# Dual_OTA_VCA.net
KiCad netlist of a schematic drawn in EAGLE
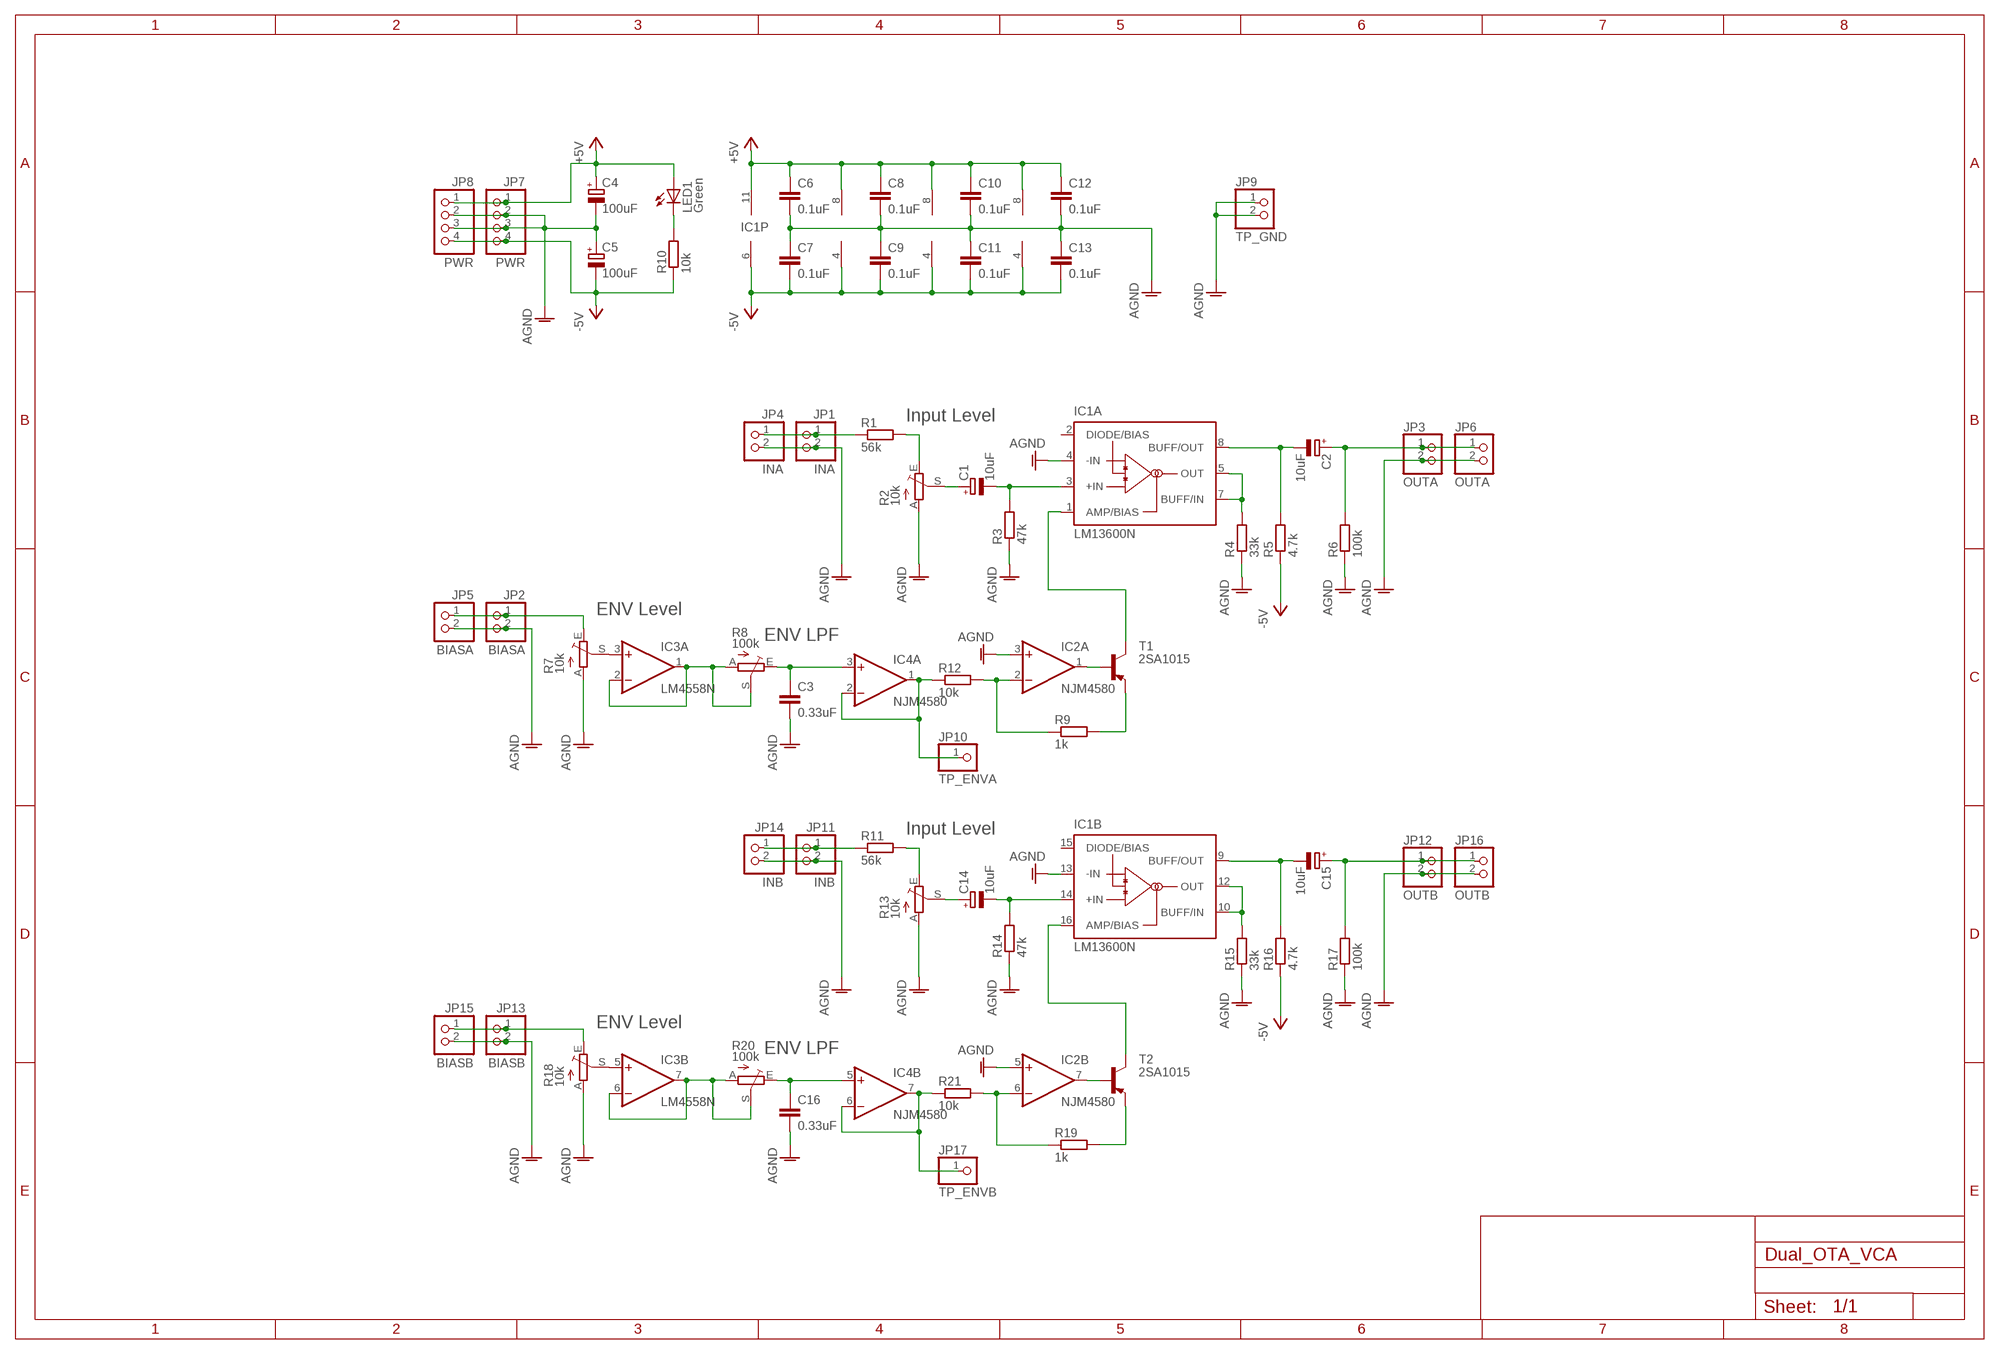
[diagram p0: schematic, sheet 1]

(export (version "E")
  (design (tool "Eeschema 10.0.6"))
  (components
    (comp (ref "C1")
      (value "10uF")
      (footprint "eagle-import:E2,5-7")
      (libsource (lib "eagle-import") (part "CPOL-EUE2.5-7"))
    )
    (comp (ref "C2")
      (value "10uF")
      (footprint "eagle-import:E2,5-7")
      (libsource (lib "eagle-import") (part "CPOL-EUE2.5-7"))
    )
    (comp (ref "C3")
      (value "0.33uF")
      (footprint "eagle-import:C050-030X075")
      (libsource (lib "eagle-import") (part "C-EU050-030X075"))
    )
    (comp (ref "C4")
      (value "100uF")
      (footprint "eagle-import:E2,5-7")
      (libsource (lib "eagle-import") (part "CPOL-EUE2.5-7"))
    )
    (comp (ref "C5")
      (value "100uF")
      (footprint "eagle-import:E2,5-7")
      (libsource (lib "eagle-import") (part "CPOL-EUE2.5-7"))
    )
    (comp (ref "C6")
      (value "0.1uF")
      (footprint "eagle-import:C050-024X044")
      (libsource (lib "eagle-import") (part "C-EU050-024X044"))
    )
    (comp (ref "C7")
      (value "0.1uF")
      (footprint "eagle-import:C050-024X044")
      (libsource (lib "eagle-import") (part "C-EU050-024X044"))
    )
    (comp (ref "C8")
      (value "0.1uF")
      (footprint "eagle-import:C025-024X044")
      (libsource (lib "eagle-import") (part "C-EU025-024X044"))
    )
    (comp (ref "C9")
      (value "0.1uF")
      (footprint "eagle-import:C025-024X044")
      (libsource (lib "eagle-import") (part "C-EU025-024X044"))
    )
    (comp (ref "C10")
      (value "0.1uF")
      (footprint "eagle-import:C025-024X044")
      (libsource (lib "eagle-import") (part "C-EU025-024X044"))
    )
    (comp (ref "C11")
      (value "0.1uF")
      (footprint "eagle-import:C025-024X044")
      (libsource (lib "eagle-import") (part "C-EU025-024X044"))
    )
    (comp (ref "C12")
      (value "0.1uF")
      (footprint "eagle-import:C025-024X044")
      (libsource (lib "eagle-import") (part "C-EU025-024X044"))
    )
    (comp (ref "C13")
      (value "0.1uF")
      (footprint "eagle-import:C025-024X044")
      (libsource (lib "eagle-import") (part "C-EU025-024X044"))
    )
    (comp (ref "C14")
      (value "10uF")
      (footprint "eagle-import:E2,5-7")
      (libsource (lib "eagle-import") (part "CPOL-EUE2.5-7"))
    )
    (comp (ref "C15")
      (value "10uF")
      (footprint "eagle-import:E2,5-7")
      (libsource (lib "eagle-import") (part "CPOL-EUE2.5-7"))
    )
    (comp (ref "C16")
      (value "0.33uF")
      (footprint "eagle-import:C050-030X075")
      (libsource (lib "eagle-import") (part "C-EU050-030X075"))
    )
    (comp (ref "IC1")
      (value "LM13600N")
      (footprint "eagle-import:DIL16")
      (libsource (lib "eagle-import") (part "LM13600N"))
    )
    (comp (ref "IC2")
      (value "NJM4580")
      (footprint "eagle-import:DIL08")
      (libsource (lib "eagle-import") (part "4558NLM"))
    )
    (comp (ref "IC3")
      (value "LM4558N")
      (footprint "eagle-import:DIL08")
      (libsource (lib "eagle-import") (part "4558NLM"))
    )
    (comp (ref "IC4")
      (value "NJM4580")
      (footprint "eagle-import:DIL08")
      (libsource (lib "eagle-import") (part "4558NLM"))
    )
    (comp (ref "JP1")
      (value "INA")
      (footprint "eagle-import:1X02")
      (libsource (lib "eagle-import") (part "PINHD-1X2"))
    )
    (comp (ref "JP2")
      (value "BIASA")
      (footprint "eagle-import:1X02")
      (libsource (lib "eagle-import") (part "PINHD-1X2"))
    )
    (comp (ref "JP3")
      (value "OUTA")
      (footprint "eagle-import:1X02")
      (libsource (lib "eagle-import") (part "PINHD-1X2"))
    )
    (comp (ref "JP4")
      (value "INA")
      (footprint "eagle-import:1X02")
      (libsource (lib "eagle-import") (part "PINHD-1X2"))
    )
    (comp (ref "JP5")
      (value "BIASA")
      (footprint "eagle-import:1X02")
      (libsource (lib "eagle-import") (part "PINHD-1X2"))
    )
    (comp (ref "JP6")
      (value "OUTA")
      (footprint "eagle-import:1X02")
      (libsource (lib "eagle-import") (part "PINHD-1X2"))
    )
    (comp (ref "JP7")
      (value "PWR")
      (footprint "eagle-import:1X04")
      (libsource (lib "eagle-import") (part "PINHD-1X4"))
    )
    (comp (ref "JP8")
      (value "PWR")
      (footprint "eagle-import:1X04")
      (libsource (lib "eagle-import") (part "PINHD-1X4"))
    )
    (comp (ref "JP9")
      (value "TP_GND")
      (footprint "eagle-import:1X02")
      (libsource (lib "eagle-import") (part "PINHD-1X2"))
    )
    (comp (ref "JP10")
      (value "TP_ENVA")
      (footprint "eagle-import:1X01")
      (libsource (lib "eagle-import") (part "PINHD-1X1"))
    )
    (comp (ref "JP11")
      (value "INB")
      (footprint "eagle-import:1X02")
      (libsource (lib "eagle-import") (part "PINHD-1X2"))
    )
    (comp (ref "JP12")
      (value "OUTB")
      (footprint "eagle-import:1X02")
      (libsource (lib "eagle-import") (part "PINHD-1X2"))
    )
    (comp (ref "JP13")
      (value "BIASB")
      (footprint "eagle-import:1X02")
      (libsource (lib "eagle-import") (part "PINHD-1X2"))
    )
    (comp (ref "JP14")
      (value "INB")
      (footprint "eagle-import:1X02")
      (libsource (lib "eagle-import") (part "PINHD-1X2"))
    )
    (comp (ref "JP15")
      (value "BIASB")
      (footprint "eagle-import:1X02")
      (libsource (lib "eagle-import") (part "PINHD-1X2"))
    )
    (comp (ref "JP16")
      (value "OUTB")
      (footprint "eagle-import:1X02")
      (libsource (lib "eagle-import") (part "PINHD-1X2"))
    )
    (comp (ref "JP17")
      (value "TP_ENVB")
      (footprint "eagle-import:1X01")
      (libsource (lib "eagle-import") (part "PINHD-1X1"))
    )
    (comp (ref "LED1")
      (value "Green")
      (footprint "eagle-import:LED3MM")
      (libsource (lib "eagle-import") (part "LED3MM"))
    )
    (comp (ref "R1")
      (value "56k")
      (footprint "eagle-import:0207_7")
      (libsource (lib "eagle-import") (part "R-EU_0207/7"))
    )
    (comp (ref "R2")
      (value "10k")
      (footprint "eagle-import:B25P")
      (libsource (lib "eagle-import") (part "TRIM_EU-B25P"))
    )
    (comp (ref "R3")
      (value "47k")
      (footprint "eagle-import:0207_7")
      (libsource (lib "eagle-import") (part "R-EU_0207/7"))
    )
    (comp (ref "R4")
      (value "33k")
      (footprint "eagle-import:0207_7")
      (libsource (lib "eagle-import") (part "R-EU_0207/7"))
    )
    (comp (ref "R5")
      (value "4.7k")
      (footprint "eagle-import:0207_7")
      (libsource (lib "eagle-import") (part "R-EU_0207/7"))
    )
    (comp (ref "R6")
      (value "100k")
      (footprint "eagle-import:0207_7")
      (libsource (lib "eagle-import") (part "R-EU_0207/7"))
    )
    (comp (ref "R7")
      (value "10k")
      (footprint "eagle-import:B25P")
      (libsource (lib "eagle-import") (part "TRIM_EU-B25P"))
    )
    (comp (ref "R8")
      (value "100k")
      (footprint "eagle-import:B25P")
      (libsource (lib "eagle-import") (part "TRIM_EU-B25P"))
    )
    (comp (ref "R9")
      (value "1k")
      (footprint "eagle-import:0207_7")
      (libsource (lib "eagle-import") (part "R-EU_0207/7"))
    )
    (comp (ref "R10")
      (value "10k")
      (footprint "eagle-import:0207_7")
      (libsource (lib "eagle-import") (part "R-EU_0207/7"))
    )
    (comp (ref "R11")
      (value "56k")
      (footprint "eagle-import:0207_7")
      (libsource (lib "eagle-import") (part "R-EU_0207/7"))
    )
    (comp (ref "R12")
      (value "10k")
      (footprint "eagle-import:0207_7")
      (libsource (lib "eagle-import") (part "R-EU_0207/7"))
    )
    (comp (ref "R13")
      (value "10k")
      (footprint "eagle-import:B25P")
      (libsource (lib "eagle-import") (part "TRIM_EU-B25P"))
    )
    (comp (ref "R14")
      (value "47k")
      (footprint "eagle-import:0207_7")
      (libsource (lib "eagle-import") (part "R-EU_0207/7"))
    )
    (comp (ref "R15")
      (value "33k")
      (footprint "eagle-import:0207_7")
      (libsource (lib "eagle-import") (part "R-EU_0207/7"))
    )
    (comp (ref "R16")
      (value "4.7k")
      (footprint "eagle-import:0207_7")
      (libsource (lib "eagle-import") (part "R-EU_0207/7"))
    )
    (comp (ref "R17")
      (value "100k")
      (footprint "eagle-import:0207_7")
      (libsource (lib "eagle-import") (part "R-EU_0207/7"))
    )
    (comp (ref "R18")
      (value "10k")
      (footprint "eagle-import:B25P")
      (libsource (lib "eagle-import") (part "TRIM_EU-B25P"))
    )
    (comp (ref "R19")
      (value "1k")
      (footprint "eagle-import:0207_7")
      (libsource (lib "eagle-import") (part "R-EU_0207/7"))
    )
    (comp (ref "R20")
      (value "100k")
      (footprint "eagle-import:B25P")
      (libsource (lib "eagle-import") (part "TRIM_EU-B25P"))
    )
    (comp (ref "R21")
      (value "10k")
      (footprint "eagle-import:0207_7")
      (libsource (lib "eagle-import") (part "R-EU_0207/7"))
    )
    (comp (ref "T1")
      (value "2SA1015")
      (footprint "eagle-import:TO92-ECB")
      (libsource (lib "eagle-import") (part "-PNP-TO92-ECB"))
    )
    (comp (ref "T2")
      (value "2SA1015")
      (footprint "eagle-import:TO92-ECB")
      (libsource (lib "eagle-import") (part "-PNP-TO92-ECB"))
    )
  )
  (nets
    (net (code "1") (name "+5V") (class "Default")
      (node (ref "C10") (pin "1") (pinfunction "1_1") (pintype "passive"))
      (node (ref "C12") (pin "1") (pinfunction "1_1") (pintype "passive"))
      (node (ref "C4") (pin "+") (pinfunction "+_+") (pintype "passive"))
      (node (ref "C6") (pin "1") (pinfunction "1_1") (pintype "passive"))
      (node (ref "C8") (pin "1") (pinfunction "1_1") (pintype "passive"))
      (node (ref "IC1") (pin "11") (pinfunction "V+_11") (pintype "power_in"))
      (node (ref "IC2") (pin "8") (pinfunction "V+_8") (pintype "power_in"))
      (node (ref "IC3") (pin "8") (pinfunction "V+_8") (pintype "power_in"))
      (node (ref "IC4") (pin "8") (pinfunction "V+_8") (pintype "power_in"))
      (node (ref "JP7") (pin "1") (pinfunction "1_1") (pintype "passive"))
      (node (ref "JP8") (pin "1") (pinfunction "1_1") (pintype "passive"))
      (node (ref "LED1") (pin "A") (pinfunction "A_A") (pintype "passive"))
    )
    (net (code "2") (name "-5V") (class "Default")
      (node (ref "C11") (pin "2") (pinfunction "2_2") (pintype "passive"))
      (node (ref "C13") (pin "2") (pinfunction "2_2") (pintype "passive"))
      (node (ref "C5") (pin "-") (pinfunction "-_-") (pintype "passive"))
      (node (ref "C7") (pin "2") (pinfunction "2_2") (pintype "passive"))
      (node (ref "C9") (pin "2") (pinfunction "2_2") (pintype "passive"))
      (node (ref "IC1") (pin "6") (pinfunction "V-_6") (pintype "power_in"))
      (node (ref "IC2") (pin "4") (pinfunction "V-_4") (pintype "power_in"))
      (node (ref "IC3") (pin "4") (pinfunction "V-_4") (pintype "power_in"))
      (node (ref "IC4") (pin "4") (pinfunction "V-_4") (pintype "power_in"))
      (node (ref "JP7") (pin "4") (pinfunction "4_4") (pintype "passive"))
      (node (ref "JP8") (pin "4") (pinfunction "4_4") (pintype "passive"))
      (node (ref "R10") (pin "1") (pinfunction "1_1") (pintype "passive"))
      (node (ref "R16") (pin "1") (pinfunction "1_1") (pintype "passive"))
      (node (ref "R5") (pin "1") (pinfunction "1_1") (pintype "passive"))
    )
    (net (code "3") (name "AGND") (class "Default")
      (node (ref "C10") (pin "2") (pinfunction "2_2") (pintype "passive"))
      (node (ref "C11") (pin "1") (pinfunction "1_1") (pintype "passive"))
      (node (ref "C12") (pin "2") (pinfunction "2_2") (pintype "passive"))
      (node (ref "C13") (pin "1") (pinfunction "1_1") (pintype "passive"))
      (node (ref "C16") (pin "2") (pinfunction "2_2") (pintype "passive"))
      (node (ref "C3") (pin "2") (pinfunction "2_2") (pintype "passive"))
      (node (ref "C4") (pin "-") (pinfunction "-_-") (pintype "passive"))
      (node (ref "C5") (pin "+") (pinfunction "+_+") (pintype "passive"))
      (node (ref "C6") (pin "2") (pinfunction "2_2") (pintype "passive"))
      (node (ref "C7") (pin "1") (pinfunction "1_1") (pintype "passive"))
      (node (ref "C8") (pin "2") (pinfunction "2_2") (pintype "passive"))
      (node (ref "C9") (pin "1") (pinfunction "1_1") (pintype "passive"))
      (node (ref "IC1") (pin "13") (pinfunction "-IN_13") (pintype "input"))
      (node (ref "IC1") (pin "4") (pinfunction "-IN_4") (pintype "input"))
      (node (ref "IC2") (pin "3") (pinfunction "+IN_3") (pintype "input"))
      (node (ref "IC2") (pin "5") (pinfunction "+IN_5") (pintype "input"))
      (node (ref "JP1") (pin "2") (pinfunction "2_2") (pintype "passive"))
      (node (ref "JP11") (pin "2") (pinfunction "2_2") (pintype "passive"))
      (node (ref "JP12") (pin "2") (pinfunction "2_2") (pintype "passive"))
      (node (ref "JP13") (pin "2") (pinfunction "2_2") (pintype "passive"))
      (node (ref "JP14") (pin "2") (pinfunction "2_2") (pintype "passive"))
      (node (ref "JP15") (pin "2") (pinfunction "2_2") (pintype "passive"))
      (node (ref "JP16") (pin "2") (pinfunction "2_2") (pintype "passive"))
      (node (ref "JP2") (pin "2") (pinfunction "2_2") (pintype "passive"))
      (node (ref "JP3") (pin "2") (pinfunction "2_2") (pintype "passive"))
      (node (ref "JP4") (pin "2") (pinfunction "2_2") (pintype "passive"))
      (node (ref "JP5") (pin "2") (pinfunction "2_2") (pintype "passive"))
      (node (ref "JP6") (pin "2") (pinfunction "2_2") (pintype "passive"))
      (node (ref "JP7") (pin "2") (pinfunction "2_2") (pintype "passive"))
      (node (ref "JP7") (pin "3") (pinfunction "3_3") (pintype "passive"))
      (node (ref "JP8") (pin "2") (pinfunction "2_2") (pintype "passive"))
      (node (ref "JP8") (pin "3") (pinfunction "3_3") (pintype "passive"))
      (node (ref "JP9") (pin "1") (pinfunction "1_1") (pintype "passive"))
      (node (ref "JP9") (pin "2") (pinfunction "2_2") (pintype "passive"))
      (node (ref "R13") (pin "A") (pinfunction "A_A") (pintype "passive"))
      (node (ref "R14") (pin "1") (pinfunction "1_1") (pintype "passive"))
      (node (ref "R15") (pin "1") (pinfunction "1_1") (pintype "passive"))
      (node (ref "R17") (pin "1") (pinfunction "1_1") (pintype "passive"))
      (node (ref "R18") (pin "A") (pinfunction "A_A") (pintype "passive"))
      (node (ref "R2") (pin "A") (pinfunction "A_A") (pintype "passive"))
      (node (ref "R3") (pin "1") (pinfunction "1_1") (pintype "passive"))
      (node (ref "R4") (pin "1") (pinfunction "1_1") (pintype "passive"))
      (node (ref "R6") (pin "1") (pinfunction "1_1") (pintype "passive"))
      (node (ref "R7") (pin "A") (pinfunction "A_A") (pintype "passive"))
    )
    (net (code "4") (name "Net-(C1-Pad+)") (class "Default")
      (node (ref "C1") (pin "+") (pinfunction "+_+") (pintype "passive"))
      (node (ref "R2") (pin "S") (pinfunction "S_S") (pintype "passive"))
    )
    (net (code "5") (name "Net-(C2-Pad+)") (class "Default")
      (node (ref "C2") (pin "+") (pinfunction "+_+") (pintype "passive"))
      (node (ref "JP3") (pin "1") (pinfunction "1_1") (pintype "passive"))
      (node (ref "JP6") (pin "1") (pinfunction "1_1") (pintype "passive"))
      (node (ref "R6") (pin "2") (pinfunction "2_2") (pintype "passive"))
    )
    (net (code "6") (name "Net-(C14-Pad+)") (class "Default")
      (node (ref "C14") (pin "+") (pinfunction "+_+") (pintype "passive"))
      (node (ref "R13") (pin "S") (pinfunction "S_S") (pintype "passive"))
    )
    (net (code "7") (name "Net-(C15-Pad+)") (class "Default")
      (node (ref "C15") (pin "+") (pinfunction "+_+") (pintype "passive"))
      (node (ref "JP12") (pin "1") (pinfunction "1_1") (pintype "passive"))
      (node (ref "JP16") (pin "1") (pinfunction "1_1") (pintype "passive"))
      (node (ref "R17") (pin "2") (pinfunction "2_2") (pintype "passive"))
    )
    (net (code "8") (name "Net-(IC1A-+IN)") (class "Default")
      (node (ref "C1") (pin "-") (pinfunction "-_-") (pintype "passive"))
      (node (ref "IC1") (pin "3") (pinfunction "+IN_3") (pintype "input"))
      (node (ref "R3") (pin "2") (pinfunction "2_2") (pintype "passive"))
    )
    (net (code "9") (name "Net-(IC1A-AMP{slash}BIAS)") (class "Default")
      (node (ref "IC1") (pin "1") (pinfunction "AMP/BIAS_1") (pintype "passive"))
      (node (ref "T1") (pin "C") (pinfunction "C_C") (pintype "passive"))
    )
    (net (code "10") (name "Net-(IC1A-BUFF{slash}IN)") (class "Default")
      (node (ref "IC1") (pin "5") (pinfunction "OUT_5") (pintype "output"))
      (node (ref "IC1") (pin "7") (pinfunction "BUFF/IN_7") (pintype "input"))
      (node (ref "R4") (pin "2") (pinfunction "2_2") (pintype "passive"))
    )
    (net (code "11") (name "Net-(IC1A-BUFF{slash}OUT)") (class "Default")
      (node (ref "C2") (pin "-") (pinfunction "-_-") (pintype "passive"))
      (node (ref "IC1") (pin "8") (pinfunction "BUFF/OUT_8") (pintype "output"))
      (node (ref "R5") (pin "2") (pinfunction "2_2") (pintype "passive"))
    )
    (net (code "12") (name "Net-(IC1B-+IN)") (class "Default")
      (node (ref "C14") (pin "-") (pinfunction "-_-") (pintype "passive"))
      (node (ref "IC1") (pin "14") (pinfunction "+IN_14") (pintype "input"))
      (node (ref "R14") (pin "2") (pinfunction "2_2") (pintype "passive"))
    )
    (net (code "13") (name "Net-(IC1B-AMP{slash}BIAS)") (class "Default")
      (node (ref "IC1") (pin "16") (pinfunction "AMP/BIAS_16") (pintype "passive"))
      (node (ref "T2") (pin "C") (pinfunction "C_C") (pintype "passive"))
    )
    (net (code "14") (name "Net-(IC1B-BUFF{slash}IN)") (class "Default")
      (node (ref "IC1") (pin "10") (pinfunction "BUFF/IN_10") (pintype "input"))
      (node (ref "IC1") (pin "12") (pinfunction "OUT_12") (pintype "output"))
      (node (ref "R15") (pin "2") (pinfunction "2_2") (pintype "passive"))
    )
    (net (code "15") (name "Net-(IC1B-BUFF{slash}OUT)") (class "Default")
      (node (ref "C15") (pin "-") (pinfunction "-_-") (pintype "passive"))
      (node (ref "IC1") (pin "9") (pinfunction "BUFF/OUT_9") (pintype "output"))
      (node (ref "R16") (pin "2") (pinfunction "2_2") (pintype "passive"))
    )
    (net (code "16") (name "Net-(IC2A--IN)") (class "Default")
      (node (ref "IC2") (pin "2") (pinfunction "-IN_2") (pintype "input"))
      (node (ref "R12") (pin "2") (pinfunction "2_2") (pintype "passive"))
      (node (ref "R9") (pin "1") (pinfunction "1_1") (pintype "passive"))
    )
    (net (code "17") (name "Net-(IC2A-OUT)") (class "Default")
      (node (ref "IC2") (pin "1") (pinfunction "OUT_1") (pintype "output"))
      (node (ref "T1") (pin "B") (pinfunction "B_B") (pintype "passive"))
    )
    (net (code "18") (name "Net-(IC2B--IN)") (class "Default")
      (node (ref "IC2") (pin "6") (pinfunction "-IN_6") (pintype "input"))
      (node (ref "R19") (pin "1") (pinfunction "1_1") (pintype "passive"))
      (node (ref "R21") (pin "2") (pinfunction "2_2") (pintype "passive"))
    )
    (net (code "19") (name "Net-(IC2B-OUT)") (class "Default")
      (node (ref "IC2") (pin "7") (pinfunction "OUT_7") (pintype "output"))
      (node (ref "T2") (pin "B") (pinfunction "B_B") (pintype "passive"))
    )
    (net (code "20") (name "Net-(IC3A-+IN)") (class "Default")
      (node (ref "IC3") (pin "3") (pinfunction "+IN_3") (pintype "input"))
      (node (ref "R7") (pin "S") (pinfunction "S_S") (pintype "passive"))
    )
    (net (code "21") (name "Net-(IC3A--IN)") (class "Default")
      (node (ref "IC3") (pin "1") (pinfunction "OUT_1") (pintype "output"))
      (node (ref "IC3") (pin "2") (pinfunction "-IN_2") (pintype "input"))
      (node (ref "R8") (pin "A") (pinfunction "A_A") (pintype "passive"))
      (node (ref "R8") (pin "S") (pinfunction "S_S") (pintype "passive"))
    )
    (net (code "22") (name "Net-(IC3B-+IN)") (class "Default")
      (node (ref "IC3") (pin "5") (pinfunction "+IN_5") (pintype "input"))
      (node (ref "R18") (pin "S") (pinfunction "S_S") (pintype "passive"))
    )
    (net (code "23") (name "Net-(IC3B--IN)") (class "Default")
      (node (ref "IC3") (pin "6") (pinfunction "-IN_6") (pintype "input"))
      (node (ref "IC3") (pin "7") (pinfunction "OUT_7") (pintype "output"))
      (node (ref "R20") (pin "A") (pinfunction "A_A") (pintype "passive"))
      (node (ref "R20") (pin "S") (pinfunction "S_S") (pintype "passive"))
    )
    (net (code "24") (name "Net-(IC4A-+IN)") (class "Default")
      (node (ref "C3") (pin "1") (pinfunction "1_1") (pintype "passive"))
      (node (ref "IC4") (pin "3") (pinfunction "+IN_3") (pintype "input"))
      (node (ref "R8") (pin "E") (pinfunction "E_E") (pintype "passive"))
    )
    (net (code "25") (name "Net-(IC4A--IN)") (class "Default")
      (node (ref "IC4") (pin "1") (pinfunction "OUT_1") (pintype "output"))
      (node (ref "IC4") (pin "2") (pinfunction "-IN_2") (pintype "input"))
      (node (ref "JP10") (pin "1") (pinfunction "1_1") (pintype "passive"))
      (node (ref "R12") (pin "1") (pinfunction "1_1") (pintype "passive"))
    )
    (net (code "26") (name "Net-(IC4B-+IN)") (class "Default")
      (node (ref "C16") (pin "1") (pinfunction "1_1") (pintype "passive"))
      (node (ref "IC4") (pin "5") (pinfunction "+IN_5") (pintype "input"))
      (node (ref "R20") (pin "E") (pinfunction "E_E") (pintype "passive"))
    )
    (net (code "27") (name "Net-(IC4B--IN)") (class "Default")
      (node (ref "IC4") (pin "6") (pinfunction "-IN_6") (pintype "input"))
      (node (ref "IC4") (pin "7") (pinfunction "OUT_7") (pintype "output"))
      (node (ref "JP17") (pin "1") (pinfunction "1_1") (pintype "passive"))
      (node (ref "R21") (pin "1") (pinfunction "1_1") (pintype "passive"))
    )
    (net (code "28") (name "Net-(JP1-Pad1)") (class "Default")
      (node (ref "JP1") (pin "1") (pinfunction "1_1") (pintype "passive"))
      (node (ref "JP4") (pin "1") (pinfunction "1_1") (pintype "passive"))
      (node (ref "R1") (pin "1") (pinfunction "1_1") (pintype "passive"))
    )
    (net (code "29") (name "Net-(JP2-Pad1)") (class "Default")
      (node (ref "JP2") (pin "1") (pinfunction "1_1") (pintype "passive"))
      (node (ref "JP5") (pin "1") (pinfunction "1_1") (pintype "passive"))
      (node (ref "R7") (pin "E") (pinfunction "E_E") (pintype "passive"))
    )
    (net (code "30") (name "Net-(JP11-Pad1)") (class "Default")
      (node (ref "JP11") (pin "1") (pinfunction "1_1") (pintype "passive"))
      (node (ref "JP14") (pin "1") (pinfunction "1_1") (pintype "passive"))
      (node (ref "R11") (pin "1") (pinfunction "1_1") (pintype "passive"))
    )
    (net (code "31") (name "Net-(JP13-Pad1)") (class "Default")
      (node (ref "JP13") (pin "1") (pinfunction "1_1") (pintype "passive"))
      (node (ref "JP15") (pin "1") (pinfunction "1_1") (pintype "passive"))
      (node (ref "R18") (pin "E") (pinfunction "E_E") (pintype "passive"))
    )
    (net (code "32") (name "Net-(LED1-C)") (class "Default")
      (node (ref "LED1") (pin "K") (pinfunction "C_K") (pintype "passive"))
      (node (ref "R10") (pin "2") (pinfunction "2_2") (pintype "passive"))
    )
    (net (code "33") (name "Net-(R1-Pad2)") (class "Default")
      (node (ref "R1") (pin "2") (pinfunction "2_2") (pintype "passive"))
      (node (ref "R2") (pin "E") (pinfunction "E_E") (pintype "passive"))
    )
    (net (code "34") (name "Net-(R9-Pad2)") (class "Default")
      (node (ref "R9") (pin "2") (pinfunction "2_2") (pintype "passive"))
      (node (ref "T1") (pin "E") (pinfunction "E_E") (pintype "passive"))
    )
    (net (code "35") (name "Net-(R11-Pad2)") (class "Default")
      (node (ref "R11") (pin "2") (pinfunction "2_2") (pintype "passive"))
      (node (ref "R13") (pin "E") (pinfunction "E_E") (pintype "passive"))
    )
    (net (code "36") (name "Net-(R19-Pad2)") (class "Default")
      (node (ref "R19") (pin "2") (pinfunction "2_2") (pintype "passive"))
      (node (ref "T2") (pin "E") (pinfunction "E_E") (pintype "passive"))
    )
    (net (code "37") (name "unconnected-(IC1A-DIODE{slash}BIAS-Pad2)") (class "Default")
      (node (ref "IC1") (pin "2") (pinfunction "DIODE/BIAS_2") (pintype "passive"))
    )
    (net (code "38") (name "unconnected-(IC1B-DIODE{slash}BIAS-Pad15)") (class "Default")
      (node (ref "IC1") (pin "15") (pinfunction "DIODE/BIAS_15") (pintype "passive"))
    )
  )
)
